# MAIN_SCH.net
KiCad netlist of a schematic drawn in Altium Designer
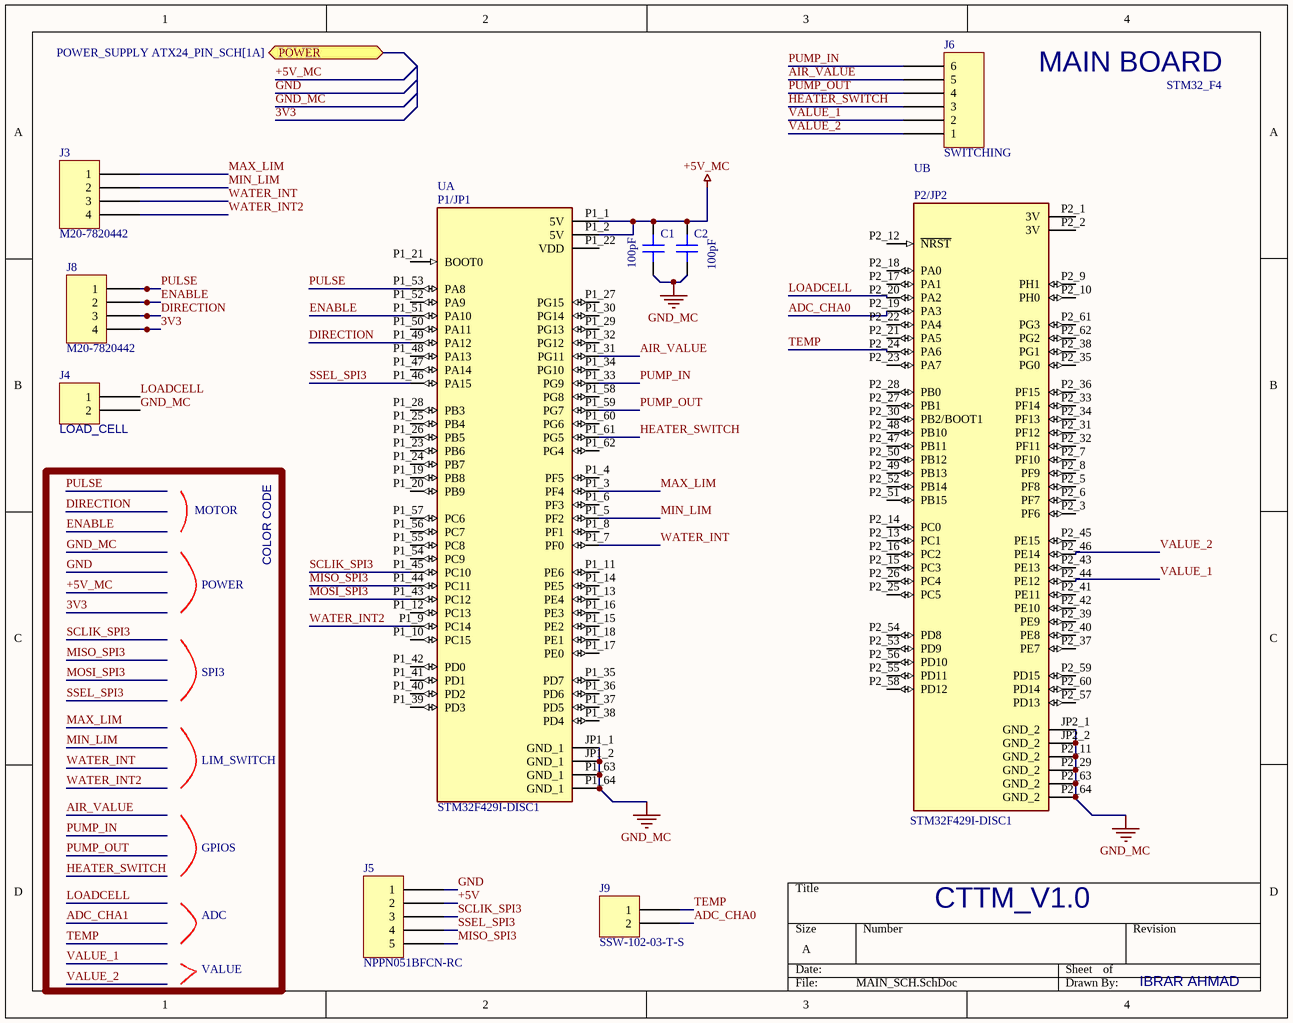
[diagram p0: MAIN_SCH.SchDoc]

(export (version "E")
  (design (tool "Eeschema 10.0.6"))
  (components
    (comp (ref "C1")
      (value "100pF")
      (footprint "CAP 1206_3216 - 0.8MM")
      (description "CAP CER 100PF 100V C0G/NP0 1206")
      (fields (field (name "PART NUMBER") "MM061A101JCT2A") (field (name "MANUFACTURER") "AVX Corporation"))
      (libsource (lib "Celestial Altium Library - altium_library") (part "Capacitor"))
    )
    (comp (ref "C2")
      (value "100pF")
      (footprint "CAP 1206_3216 - 0.8MM")
      (description "CAP CER 100PF 100V C0G/NP0 1206")
      (fields (field (name "PART NUMBER") "MM061A101JCT2A") (field (name "MANUFACTURER") "AVX Corporation"))
      (libsource (lib "Celestial Altium Library - altium_library") (part "Capacitor"))
    )
    (comp (ref "J3")
      (value "M20-7820442")
      (footprint "HARWIN M20-7820445")
      (description "CONN RCPT 4POS 0.1 GOLD PCB")
      (fields (field (name "MANUFACTURER") "Harwin Inc."))
      (libsource (lib "Celestial Altium Library - altium_library") (part "4 Pin"))
    )
    (comp (ref "J4")
      (value "LOAD_CELL")
      (footprint "SAMTEC SSW-102-03-T-S")
      (description "CONN RCPT 2POS 0.1 TIN PCB")
      (fields (field (name "PART NUMBER") "SSW-102-03-T-S") (field (name "MANUFACTURER") "Samtec Inc."))
      (libsource (lib "Celestial Altium Library - altium_library") (part "2 Pin"))
    )
    (comp (ref "J5")
      (value "NPPN051BFCN-RC")
      (footprint "SULLINS NPPN051BFCN")
      (description "CONN HDR 5POS 0.079 GOLD PCB")
      (fields (field (name "MANUFACTURER") "Sullins Connector Solutions"))
      (libsource (lib "Celestial Altium Library - altium_library") (part "5 Pin"))
    )
    (comp (ref "J6")
      (value "SWITCHING")
      (footprint "MOLEX KK 0022272061")
      (description "CONN HEADER VERT 6POS 2.54MM")
      (fields (field (name "PART NUMBER") "0022272061") (field (name "MANUFACTURER") "Molex"))
      (libsource (lib "Celestial Altium Library - altium_library") (part "6 Pin"))
    )
    (comp (ref "J8")
      (value "M20-7820442")
      (footprint "HARWIN M20-7820445")
      (description "CONN RCPT 4POS 0.1 GOLD PCB")
      (fields (field (name "MANUFACTURER") "Harwin Inc."))
      (libsource (lib "Celestial Altium Library - altium_library") (part "4 Pin"))
    )
    (comp (ref "J9")
      (value "SSW-102-03-T-S")
      (footprint "SAMTEC SSW-102-03-T-S")
      (description "CONN RCPT 2POS 0.1 TIN PCB")
      (fields (field (name "MANUFACTURER") "Samtec Inc."))
      (libsource (lib "Celestial Altium Library - altium_library") (part "2 Pin"))
    )
    (comp (ref "U")
      (value "STM32F429I-DISC1")
      (footprint "MODULE_STM32F429I-DISC1")
      (description "STM32F429 Discovery STM32F4 ARMÂ® CortexÂ®-M4 MCU 32-Bit Embedded Evaluation Board")
      (fields (field (name "MF") "STMicroelectronics"))
      (libsource (lib "STM32F429I-DISC1 (1)") (part "STM32F429I-DISC1"))
    )
  )
  (nets
    (net (code "1") (name "+5V_MC") (class "Default")
      (node (ref "C1") (pin "2") (pinfunction "2_2") (pintype "passive"))
      (node (ref "C2") (pin "2") (pinfunction "2_2") (pintype "passive"))
      (node (ref "U") (pin "P1_1") (pinfunction "5V_P1_1") (pintype "power_in"))
      (node (ref "U") (pin "P1_2") (pinfunction "5V_P1_2") (pintype "power_in"))
    )
    (net (code "2") (name "/+5V") (class "Default")
      (node (ref "J5") (pin "2") (pinfunction "2_2") (pintype "passive"))
    )
    (net (code "3") (name "/3V3") (class "Default")
      (node (ref "J8") (pin "4") (pinfunction "4_4") (pintype "passive"))
    )
    (net (code "4") (name "/ADC_CHA0") (class "Default")
      (node (ref "J9") (pin "2") (pinfunction "2_2") (pintype "passive"))
      (node (ref "U") (pin "P2_19") (pinfunction "PA3_P2_19") (pintype "bidirectional"))
    )
    (net (code "6") (name "/AIR_VALUE") (class "Default")
      (node (ref "J6") (pin "5") (pinfunction "5_5") (pintype "passive"))
      (node (ref "U") (pin "P1_31") (pinfunction "PG11_P1_31") (pintype "bidirectional"))
    )
    (net (code "7") (name "/DIRECTION") (class "Default")
      (node (ref "J8") (pin "3") (pinfunction "3_3") (pintype "passive"))
      (node (ref "U") (pin "P1_49") (pinfunction "PA12_P1_49") (pintype "bidirectional"))
    )
    (net (code "8") (name "/ENABLE") (class "Default")
      (node (ref "J8") (pin "2") (pinfunction "2_2") (pintype "passive"))
      (node (ref "U") (pin "P1_51") (pinfunction "PA10_P1_51") (pintype "bidirectional"))
    )
    (net (code "9") (name "/GND") (class "Default")
      (node (ref "J5") (pin "1") (pinfunction "1_1") (pintype "passive"))
    )
    (net (code "10") (name "/HEATER_SWITCH") (class "Default")
      (node (ref "J6") (pin "3") (pinfunction "3_3") (pintype "passive"))
      (node (ref "U") (pin "P1_61") (pinfunction "PG5_P1_61") (pintype "bidirectional"))
    )
    (net (code "11") (name "/LOADCELL") (class "Default")
      (node (ref "J4") (pin "1") (pinfunction "1_1") (pintype "passive"))
      (node (ref "U") (pin "P2_20") (pinfunction "PA2_P2_20") (pintype "bidirectional"))
    )
    (net (code "12") (name "/MAX_LIM") (class "Default")
      (node (ref "J3") (pin "1") (pinfunction "1_1") (pintype "passive"))
      (node (ref "U") (pin "P1_3") (pinfunction "PF4_P1_3") (pintype "bidirectional"))
    )
    (net (code "13") (name "/MIN_LIM") (class "Default")
      (node (ref "J3") (pin "2") (pinfunction "2_2") (pintype "passive"))
      (node (ref "U") (pin "P1_5") (pinfunction "PF2_P1_5") (pintype "bidirectional"))
    )
    (net (code "14") (name "/MISO_SPI3") (class "Default")
      (node (ref "J5") (pin "5") (pinfunction "5_5") (pintype "passive"))
      (node (ref "U") (pin "P1_44") (pinfunction "PC11_P1_44") (pintype "bidirectional"))
    )
    (net (code "15") (name "/MOSI_SPI3") (class "Default")
      (node (ref "U") (pin "P1_43") (pinfunction "PC12_P1_43") (pintype "bidirectional"))
    )
    (net (code "17") (name "/PULSE") (class "Default")
      (node (ref "J8") (pin "1") (pinfunction "1_1") (pintype "passive"))
      (node (ref "U") (pin "P1_53") (pinfunction "PA8_P1_53") (pintype "bidirectional"))
    )
    (net (code "18") (name "/PUMP_IN") (class "Default")
      (node (ref "J6") (pin "6") (pinfunction "6_6") (pintype "passive"))
      (node (ref "U") (pin "P1_33") (pinfunction "PG9_P1_33") (pintype "bidirectional"))
    )
    (net (code "19") (name "/PUMP_OUT") (class "Default")
      (node (ref "J6") (pin "4") (pinfunction "4_4") (pintype "passive"))
      (node (ref "U") (pin "P1_59") (pinfunction "PG7_P1_59") (pintype "bidirectional"))
    )
    (net (code "20") (name "/SCLIK_SPI3") (class "Default")
      (node (ref "J5") (pin "3") (pinfunction "3_3") (pintype "passive"))
      (node (ref "U") (pin "P1_45") (pinfunction "PC10_P1_45") (pintype "bidirectional"))
    )
    (net (code "21") (name "/SSEL_SPI3") (class "Default")
      (node (ref "J5") (pin "4") (pinfunction "4_4") (pintype "passive"))
      (node (ref "U") (pin "P1_46") (pinfunction "PA15_P1_46") (pintype "bidirectional"))
    )
    (net (code "22") (name "/TEMP") (class "Default")
      (node (ref "J9") (pin "1") (pinfunction "1_1") (pintype "passive"))
      (node (ref "U") (pin "P2_24") (pinfunction "PA6_P2_24") (pintype "bidirectional"))
    )
    (net (code "23") (name "/VALUE_1") (class "Default")
      (node (ref "J6") (pin "2") (pinfunction "2_2") (pintype "passive"))
      (node (ref "U") (pin "P2_44") (pinfunction "PE12_P2_44") (pintype "bidirectional"))
    )
    (net (code "24") (name "/VALUE_2") (class "Default")
      (node (ref "J6") (pin "1") (pinfunction "1_1") (pintype "passive"))
      (node (ref "U") (pin "P2_46") (pinfunction "PE14_P2_46") (pintype "bidirectional"))
    )
    (net (code "25") (name "/WATER_INT") (class "Default")
      (node (ref "J3") (pin "3") (pinfunction "3_3") (pintype "passive"))
      (node (ref "U") (pin "P1_7") (pinfunction "PF0_P1_7") (pintype "bidirectional"))
    )
    (net (code "26") (name "/WATER_INT2") (class "Default")
      (node (ref "J3") (pin "4") (pinfunction "4_4") (pintype "passive"))
      (node (ref "U") (pin "P1_9") (pinfunction "PC14_P1_9") (pintype "bidirectional"))
    )
    (net (code "27") (name "GND_MC") (class "Default")
      (node (ref "C1") (pin "1") (pinfunction "1_1") (pintype "passive"))
      (node (ref "C2") (pin "1") (pinfunction "1_1") (pintype "passive"))
      (node (ref "J4") (pin "2") (pinfunction "2_2") (pintype "passive"))
      (node (ref "U") (pin "JP1_1") (pinfunction "GND_1_JP1_1") (pintype "power_in"))
      (node (ref "U") (pin "JP1_2") (pinfunction "GND_1_JP1_2") (pintype "power_in"))
      (node (ref "U") (pin "JP2_1") (pinfunction "GND_2_JP2_1") (pintype "power_in"))
      (node (ref "U") (pin "JP2_2") (pinfunction "GND_2_JP2_2") (pintype "power_in"))
      (node (ref "U") (pin "P1_63") (pinfunction "GND_1_P1_63") (pintype "power_in"))
      (node (ref "U") (pin "P1_64") (pinfunction "GND_1_P1_64") (pintype "power_in"))
      (node (ref "U") (pin "P2_11") (pinfunction "GND_2_P2_11") (pintype "power_in"))
      (node (ref "U") (pin "P2_29") (pinfunction "GND_2_P2_29") (pintype "power_in"))
      (node (ref "U") (pin "P2_63") (pinfunction "GND_2_P2_63") (pintype "power_in"))
      (node (ref "U") (pin "P2_64") (pinfunction "GND_2_P2_64") (pintype "power_in"))
    )
    (net (code "28") (name "unconnected-(UA-BOOT0-PadP1_21)") (class "Default")
      (node (ref "U") (pin "P1_21") (pinfunction "BOOT0_P1_21") (pintype "input"))
    )
    (net (code "29") (name "unconnected-(UA-PA9-PadP1_52)") (class "Default")
      (node (ref "U") (pin "P1_52") (pinfunction "PA9_P1_52") (pintype "bidirectional"))
    )
    (net (code "30") (name "unconnected-(UA-PA11-PadP1_50)") (class "Default")
      (node (ref "U") (pin "P1_50") (pinfunction "PA11_P1_50") (pintype "bidirectional"))
    )
    (net (code "31") (name "unconnected-(UA-PA13-PadP1_48)") (class "Default")
      (node (ref "U") (pin "P1_48") (pinfunction "PA13_P1_48") (pintype "bidirectional"))
    )
    (net (code "32") (name "unconnected-(UA-PA14-PadP1_47)") (class "Default")
      (node (ref "U") (pin "P1_47") (pinfunction "PA14_P1_47") (pintype "bidirectional"))
    )
    (net (code "33") (name "unconnected-(UA-PB3-PadP1_28)") (class "Default")
      (node (ref "U") (pin "P1_28") (pinfunction "PB3_P1_28") (pintype "bidirectional"))
    )
    (net (code "34") (name "unconnected-(UA-PB4-PadP1_25)") (class "Default")
      (node (ref "U") (pin "P1_25") (pinfunction "PB4_P1_25") (pintype "bidirectional"))
    )
    (net (code "35") (name "unconnected-(UA-PB5-PadP1_26)") (class "Default")
      (node (ref "U") (pin "P1_26") (pinfunction "PB5_P1_26") (pintype "bidirectional"))
    )
    (net (code "36") (name "unconnected-(UA-PB6-PadP1_23)") (class "Default")
      (node (ref "U") (pin "P1_23") (pinfunction "PB6_P1_23") (pintype "bidirectional"))
    )
    (net (code "37") (name "unconnected-(UA-PB7-PadP1_24)") (class "Default")
      (node (ref "U") (pin "P1_24") (pinfunction "PB7_P1_24") (pintype "bidirectional"))
    )
    (net (code "38") (name "unconnected-(UA-PB8-PadP1_19)") (class "Default")
      (node (ref "U") (pin "P1_19") (pinfunction "PB8_P1_19") (pintype "bidirectional"))
    )
    (net (code "39") (name "unconnected-(UA-PB9-PadP1_20)") (class "Default")
      (node (ref "U") (pin "P1_20") (pinfunction "PB9_P1_20") (pintype "bidirectional"))
    )
    (net (code "40") (name "unconnected-(UA-PC6-PadP1_57)") (class "Default")
      (node (ref "U") (pin "P1_57") (pinfunction "PC6_P1_57") (pintype "bidirectional"))
    )
    (net (code "41") (name "unconnected-(UA-PC7-PadP1_56)") (class "Default")
      (node (ref "U") (pin "P1_56") (pinfunction "PC7_P1_56") (pintype "bidirectional"))
    )
    (net (code "42") (name "unconnected-(UA-PC8-PadP1_55)") (class "Default")
      (node (ref "U") (pin "P1_55") (pinfunction "PC8_P1_55") (pintype "bidirectional"))
    )
    (net (code "43") (name "unconnected-(UA-PC9-PadP1_54)") (class "Default")
      (node (ref "U") (pin "P1_54") (pinfunction "PC9_P1_54") (pintype "bidirectional"))
    )
    (net (code "44") (name "unconnected-(UA-PC13-PadP1_12)") (class "Default")
      (node (ref "U") (pin "P1_12") (pinfunction "PC13_P1_12") (pintype "bidirectional"))
    )
    (net (code "45") (name "unconnected-(UA-PC15-PadP1_10)") (class "Default")
      (node (ref "U") (pin "P1_10") (pinfunction "PC15_P1_10") (pintype "bidirectional"))
    )
    (net (code "46") (name "unconnected-(UA-PD0-PadP1_42)") (class "Default")
      (node (ref "U") (pin "P1_42") (pinfunction "PD0_P1_42") (pintype "bidirectional"))
    )
    (net (code "47") (name "unconnected-(UA-PD1-PadP1_41)") (class "Default")
      (node (ref "U") (pin "P1_41") (pinfunction "PD1_P1_41") (pintype "bidirectional"))
    )
    (net (code "48") (name "unconnected-(UA-PD2-PadP1_40)") (class "Default")
      (node (ref "U") (pin "P1_40") (pinfunction "PD2_P1_40") (pintype "bidirectional"))
    )
    (net (code "49") (name "unconnected-(UA-PD3-PadP1_39)") (class "Default")
      (node (ref "U") (pin "P1_39") (pinfunction "PD3_P1_39") (pintype "bidirectional"))
    )
    (net (code "50") (name "unconnected-(UA-PD4-PadP1_38)") (class "Default")
      (node (ref "U") (pin "P1_38") (pinfunction "PD4_P1_38") (pintype "bidirectional"))
    )
    (net (code "51") (name "unconnected-(UA-PD5-PadP1_37)") (class "Default")
      (node (ref "U") (pin "P1_37") (pinfunction "PD5_P1_37") (pintype "bidirectional"))
    )
    (net (code "52") (name "unconnected-(UA-PD6-PadP1_36)") (class "Default")
      (node (ref "U") (pin "P1_36") (pinfunction "PD6_P1_36") (pintype "bidirectional"))
    )
    (net (code "53") (name "unconnected-(UA-PD7-PadP1_35)") (class "Default")
      (node (ref "U") (pin "P1_35") (pinfunction "PD7_P1_35") (pintype "bidirectional"))
    )
    (net (code "54") (name "unconnected-(UA-PE0-PadP1_17)") (class "Default")
      (node (ref "U") (pin "P1_17") (pinfunction "PE0_P1_17") (pintype "bidirectional"))
    )
    (net (code "55") (name "unconnected-(UA-PE1-PadP1_18)") (class "Default")
      (node (ref "U") (pin "P1_18") (pinfunction "PE1_P1_18") (pintype "bidirectional"))
    )
    (net (code "56") (name "unconnected-(UA-PE2-PadP1_15)") (class "Default")
      (node (ref "U") (pin "P1_15") (pinfunction "PE2_P1_15") (pintype "bidirectional"))
    )
    (net (code "57") (name "unconnected-(UA-PE3-PadP1_16)") (class "Default")
      (node (ref "U") (pin "P1_16") (pinfunction "PE3_P1_16") (pintype "bidirectional"))
    )
    (net (code "58") (name "unconnected-(UA-PE4-PadP1_13)") (class "Default")
      (node (ref "U") (pin "P1_13") (pinfunction "PE4_P1_13") (pintype "bidirectional"))
    )
    (net (code "59") (name "unconnected-(UA-PE5-PadP1_14)") (class "Default")
      (node (ref "U") (pin "P1_14") (pinfunction "PE5_P1_14") (pintype "bidirectional"))
    )
    (net (code "60") (name "unconnected-(UA-PE6-PadP1_11)") (class "Default")
      (node (ref "U") (pin "P1_11") (pinfunction "PE6_P1_11") (pintype "bidirectional"))
    )
    (net (code "61") (name "unconnected-(UA-PF1-PadP1_8)") (class "Default")
      (node (ref "U") (pin "P1_8") (pinfunction "PF1_P1_8") (pintype "bidirectional"))
    )
    (net (code "62") (name "unconnected-(UA-PF3-PadP1_6)") (class "Default")
      (node (ref "U") (pin "P1_6") (pinfunction "PF3_P1_6") (pintype "bidirectional"))
    )
    (net (code "63") (name "unconnected-(UA-PF5-PadP1_4)") (class "Default")
      (node (ref "U") (pin "P1_4") (pinfunction "PF5_P1_4") (pintype "bidirectional"))
    )
    (net (code "64") (name "unconnected-(UA-PG4-PadP1_62)") (class "Default")
      (node (ref "U") (pin "P1_62") (pinfunction "PG4_P1_62") (pintype "bidirectional"))
    )
    (net (code "65") (name "unconnected-(UA-PG6-PadP1_60)") (class "Default")
      (node (ref "U") (pin "P1_60") (pinfunction "PG6_P1_60") (pintype "bidirectional"))
    )
    (net (code "66") (name "unconnected-(UA-PG8-PadP1_58)") (class "Default")
      (node (ref "U") (pin "P1_58") (pinfunction "PG8_P1_58") (pintype "bidirectional"))
    )
    (net (code "67") (name "unconnected-(UA-PG10-PadP1_34)") (class "Default")
      (node (ref "U") (pin "P1_34") (pinfunction "PG10_P1_34") (pintype "bidirectional"))
    )
    (net (code "68") (name "unconnected-(UA-PG12-PadP1_32)") (class "Default")
      (node (ref "U") (pin "P1_32") (pinfunction "PG12_P1_32") (pintype "bidirectional"))
    )
    (net (code "69") (name "unconnected-(UA-PG13-PadP1_29)") (class "Default")
      (node (ref "U") (pin "P1_29") (pinfunction "PG13_P1_29") (pintype "bidirectional"))
    )
    (net (code "70") (name "unconnected-(UA-PG14-PadP1_30)") (class "Default")
      (node (ref "U") (pin "P1_30") (pinfunction "PG14_P1_30") (pintype "bidirectional"))
    )
    (net (code "71") (name "unconnected-(UA-PG15-PadP1_27)") (class "Default")
      (node (ref "U") (pin "P1_27") (pinfunction "PG15_P1_27") (pintype "bidirectional"))
    )
    (net (code "72") (name "unconnected-(UA-VDD-PadP1_22)") (class "Default")
      (node (ref "U") (pin "P1_22") (pinfunction "VDD_P1_22") (pintype "power_in"))
    )
    (net (code "73") (name "unconnected-(UB-3V-PadP2_1)") (class "Default")
      (node (ref "U") (pin "P2_1") (pinfunction "3V_P2_1") (pintype "power_in"))
    )
    (net (code "74") (name "unconnected-(UB-3V-PadP2_2)") (class "Default")
      (node (ref "U") (pin "P2_2") (pinfunction "3V_P2_2") (pintype "power_in"))
    )
    (net (code "75") (name "unconnected-(UB-PA0-PadP2_18)") (class "Default")
      (node (ref "U") (pin "P2_18") (pinfunction "PA0_P2_18") (pintype "bidirectional"))
    )
    (net (code "76") (name "unconnected-(UB-PA1-PadP2_17)") (class "Default")
      (node (ref "U") (pin "P2_17") (pinfunction "PA1_P2_17") (pintype "bidirectional"))
    )
    (net (code "77") (name "unconnected-(UB-PA4-PadP2_22)") (class "Default")
      (node (ref "U") (pin "P2_22") (pinfunction "PA4_P2_22") (pintype "bidirectional"))
    )
    (net (code "78") (name "unconnected-(UB-PA5-PadP2_21)") (class "Default")
      (node (ref "U") (pin "P2_21") (pinfunction "PA5_P2_21") (pintype "bidirectional"))
    )
    (net (code "79") (name "unconnected-(UB-PA7-PadP2_23)") (class "Default")
      (node (ref "U") (pin "P2_23") (pinfunction "PA7_P2_23") (pintype "bidirectional"))
    )
    (net (code "80") (name "unconnected-(UB-PB0-PadP2_28)") (class "Default")
      (node (ref "U") (pin "P2_28") (pinfunction "PB0_P2_28") (pintype "bidirectional"))
    )
    (net (code "81") (name "unconnected-(UB-PB1-PadP2_27)") (class "Default")
      (node (ref "U") (pin "P2_27") (pinfunction "PB1_P2_27") (pintype "bidirectional"))
    )
    (net (code "82") (name "unconnected-(UB-PB2{slash}BOOT1-PadP2_30)") (class "Default")
      (node (ref "U") (pin "P2_30") (pinfunction "PB2/BOOT1_P2_30") (pintype "bidirectional"))
    )
    (net (code "83") (name "unconnected-(UB-PB10-PadP2_48)") (class "Default")
      (node (ref "U") (pin "P2_48") (pinfunction "PB10_P2_48") (pintype "bidirectional"))
    )
    (net (code "84") (name "unconnected-(UB-PB11-PadP2_47)") (class "Default")
      (node (ref "U") (pin "P2_47") (pinfunction "PB11_P2_47") (pintype "bidirectional"))
    )
    (net (code "85") (name "unconnected-(UB-PB12-PadP2_50)") (class "Default")
      (node (ref "U") (pin "P2_50") (pinfunction "PB12_P2_50") (pintype "bidirectional"))
    )
    (net (code "86") (name "unconnected-(UB-PB13-PadP2_49)") (class "Default")
      (node (ref "U") (pin "P2_49") (pinfunction "PB13_P2_49") (pintype "bidirectional"))
    )
    (net (code "87") (name "unconnected-(UB-PB14-PadP2_52)") (class "Default")
      (node (ref "U") (pin "P2_52") (pinfunction "PB14_P2_52") (pintype "bidirectional"))
    )
    (net (code "88") (name "unconnected-(UB-PB15-PadP2_51)") (class "Default")
      (node (ref "U") (pin "P2_51") (pinfunction "PB15_P2_51") (pintype "bidirectional"))
    )
    (net (code "89") (name "unconnected-(UB-PC0-PadP2_14)") (class "Default")
      (node (ref "U") (pin "P2_14") (pinfunction "PC0_P2_14") (pintype "bidirectional"))
    )
    (net (code "90") (name "unconnected-(UB-PC1-PadP2_13)") (class "Default")
      (node (ref "U") (pin "P2_13") (pinfunction "PC1_P2_13") (pintype "bidirectional"))
    )
    (net (code "91") (name "unconnected-(UB-PC2-PadP2_16)") (class "Default")
      (node (ref "U") (pin "P2_16") (pinfunction "PC2_P2_16") (pintype "bidirectional"))
    )
    (net (code "92") (name "unconnected-(UB-PC3-PadP2_15)") (class "Default")
      (node (ref "U") (pin "P2_15") (pinfunction "PC3_P2_15") (pintype "bidirectional"))
    )
    (net (code "93") (name "unconnected-(UB-PC4-PadP2_26)") (class "Default")
      (node (ref "U") (pin "P2_26") (pinfunction "PC4_P2_26") (pintype "bidirectional"))
    )
    (net (code "94") (name "unconnected-(UB-PC5-PadP2_25)") (class "Default")
      (node (ref "U") (pin "P2_25") (pinfunction "PC5_P2_25") (pintype "bidirectional"))
    )
    (net (code "95") (name "unconnected-(UB-PD8-PadP2_54)") (class "Default")
      (node (ref "U") (pin "P2_54") (pinfunction "PD8_P2_54") (pintype "bidirectional"))
    )
    (net (code "96") (name "unconnected-(UB-PD9-PadP2_53)") (class "Default")
      (node (ref "U") (pin "P2_53") (pinfunction "PD9_P2_53") (pintype "bidirectional"))
    )
    (net (code "97") (name "unconnected-(UB-PD10-PadP2_56)") (class "Default")
      (node (ref "U") (pin "P2_56") (pinfunction "PD10_P2_56") (pintype "bidirectional"))
    )
    (net (code "98") (name "unconnected-(UB-PD11-PadP2_55)") (class "Default")
      (node (ref "U") (pin "P2_55") (pinfunction "PD11_P2_55") (pintype "bidirectional"))
    )
    (net (code "99") (name "unconnected-(UB-PD12-PadP2_58)") (class "Default")
      (node (ref "U") (pin "P2_58") (pinfunction "PD12_P2_58") (pintype "bidirectional"))
    )
    (net (code "100") (name "unconnected-(UB-PD13-PadP2_57)") (class "Default")
      (node (ref "U") (pin "P2_57") (pinfunction "PD13_P2_57") (pintype "bidirectional"))
    )
    (net (code "101") (name "unconnected-(UB-PD14-PadP2_60)") (class "Default")
      (node (ref "U") (pin "P2_60") (pinfunction "PD14_P2_60") (pintype "bidirectional"))
    )
    (net (code "102") (name "unconnected-(UB-PD15-PadP2_59)") (class "Default")
      (node (ref "U") (pin "P2_59") (pinfunction "PD15_P2_59") (pintype "bidirectional"))
    )
    (net (code "103") (name "unconnected-(UB-PE7-PadP2_37)") (class "Default")
      (node (ref "U") (pin "P2_37") (pinfunction "PE7_P2_37") (pintype "bidirectional"))
    )
    (net (code "104") (name "unconnected-(UB-PE8-PadP2_40)") (class "Default")
      (node (ref "U") (pin "P2_40") (pinfunction "PE8_P2_40") (pintype "bidirectional"))
    )
    (net (code "105") (name "unconnected-(UB-PE9-PadP2_39)") (class "Default")
      (node (ref "U") (pin "P2_39") (pinfunction "PE9_P2_39") (pintype "bidirectional"))
    )
    (net (code "106") (name "unconnected-(UB-PE10-PadP2_42)") (class "Default")
      (node (ref "U") (pin "P2_42") (pinfunction "PE10_P2_42") (pintype "bidirectional"))
    )
    (net (code "107") (name "unconnected-(UB-PE11-PadP2_41)") (class "Default")
      (node (ref "U") (pin "P2_41") (pinfunction "PE11_P2_41") (pintype "bidirectional"))
    )
    (net (code "108") (name "unconnected-(UB-PE13-PadP2_43)") (class "Default")
      (node (ref "U") (pin "P2_43") (pinfunction "PE13_P2_43") (pintype "bidirectional"))
    )
    (net (code "109") (name "unconnected-(UB-PE15-PadP2_45)") (class "Default")
      (node (ref "U") (pin "P2_45") (pinfunction "PE15_P2_45") (pintype "bidirectional"))
    )
    (net (code "110") (name "unconnected-(UB-PF6-PadP2_3)") (class "Default")
      (node (ref "U") (pin "P2_3") (pinfunction "PF6_P2_3") (pintype "bidirectional"))
    )
    (net (code "111") (name "unconnected-(UB-PF7-PadP2_6)") (class "Default")
      (node (ref "U") (pin "P2_6") (pinfunction "PF7_P2_6") (pintype "bidirectional"))
    )
    (net (code "112") (name "unconnected-(UB-PF8-PadP2_5)") (class "Default")
      (node (ref "U") (pin "P2_5") (pinfunction "PF8_P2_5") (pintype "bidirectional"))
    )
    (net (code "113") (name "unconnected-(UB-PF9-PadP2_8)") (class "Default")
      (node (ref "U") (pin "P2_8") (pinfunction "PF9_P2_8") (pintype "bidirectional"))
    )
    (net (code "114") (name "unconnected-(UB-PF10-PadP2_7)") (class "Default")
      (node (ref "U") (pin "P2_7") (pinfunction "PF10_P2_7") (pintype "bidirectional"))
    )
    (net (code "115") (name "unconnected-(UB-PF11-PadP2_32)") (class "Default")
      (node (ref "U") (pin "P2_32") (pinfunction "PF11_P2_32") (pintype "bidirectional"))
    )
    (net (code "116") (name "unconnected-(UB-PF12-PadP2_31)") (class "Default")
      (node (ref "U") (pin "P2_31") (pinfunction "PF12_P2_31") (pintype "bidirectional"))
    )
    (net (code "117") (name "unconnected-(UB-PF13-PadP2_34)") (class "Default")
      (node (ref "U") (pin "P2_34") (pinfunction "PF13_P2_34") (pintype "bidirectional"))
    )
    (net (code "118") (name "unconnected-(UB-PF14-PadP2_33)") (class "Default")
      (node (ref "U") (pin "P2_33") (pinfunction "PF14_P2_33") (pintype "bidirectional"))
    )
    (net (code "119") (name "unconnected-(UB-PF15-PadP2_36)") (class "Default")
      (node (ref "U") (pin "P2_36") (pinfunction "PF15_P2_36") (pintype "bidirectional"))
    )
    (net (code "120") (name "unconnected-(UB-PG0-PadP2_35)") (class "Default")
      (node (ref "U") (pin "P2_35") (pinfunction "PG0_P2_35") (pintype "bidirectional"))
    )
    (net (code "121") (name "unconnected-(UB-PG1-PadP2_38)") (class "Default")
      (node (ref "U") (pin "P2_38") (pinfunction "PG1_P2_38") (pintype "bidirectional"))
    )
    (net (code "122") (name "unconnected-(UB-PG2-PadP2_62)") (class "Default")
      (node (ref "U") (pin "P2_62") (pinfunction "PG2_P2_62") (pintype "bidirectional"))
    )
    (net (code "123") (name "unconnected-(UB-PG3-PadP2_61)") (class "Default")
      (node (ref "U") (pin "P2_61") (pinfunction "PG3_P2_61") (pintype "bidirectional"))
    )
    (net (code "124") (name "unconnected-(UB-PH0-PadP2_10)") (class "Default")
      (node (ref "U") (pin "P2_10") (pinfunction "PH0_P2_10") (pintype "bidirectional"))
    )
    (net (code "125") (name "unconnected-(UB-PH1-PadP2_9)") (class "Default")
      (node (ref "U") (pin "P2_9") (pinfunction "PH1_P2_9") (pintype "bidirectional"))
    )
    (net (code "126") (name "unconnected-(UB-~{NRST}-PadP2_12)") (class "Default")
      (node (ref "U") (pin "P2_12") (pinfunction "~{NRST}_P2_12") (pintype "input"))
    )
  )
)
